# FLASH_S29GL128P11FFI010_128Mbit.net
KiCad netlist of a schematic drawn in Altium Designer
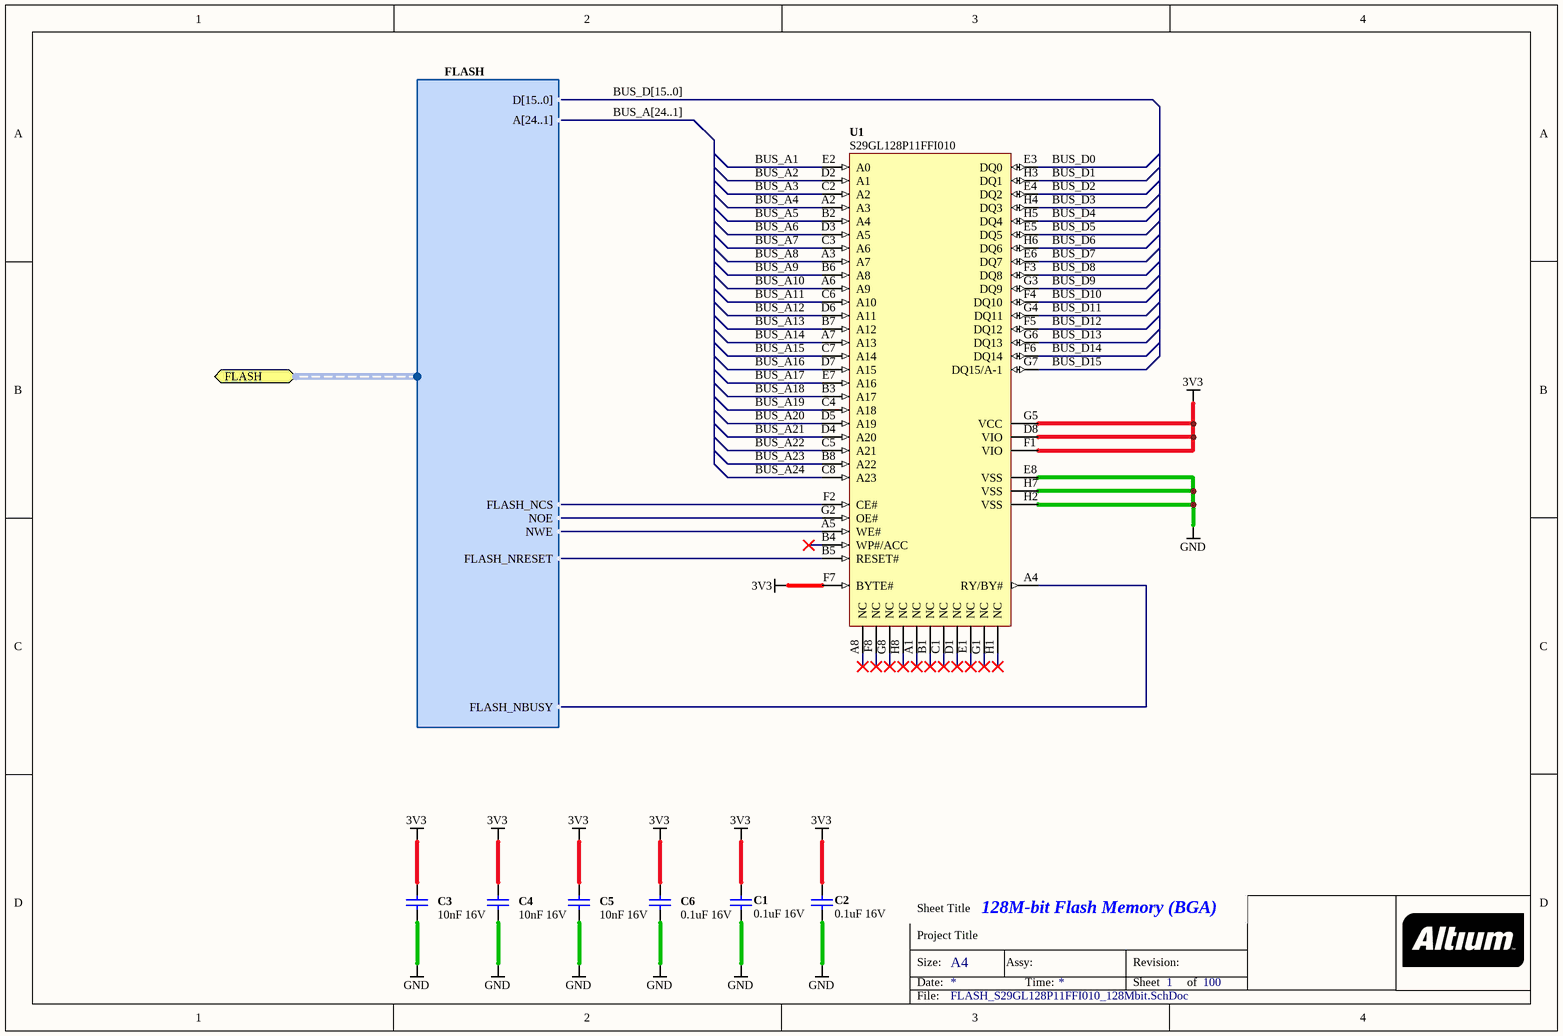
[diagram p0: FLASH_S29GL128P11FFI010_128Mbit.SchDoc]

(export (version "E")
  (design (tool "Eeschema 10.0.6"))
  (components
    (comp (ref "C1")
      (value "0.1uF 16V")
      (footprint "CAPC1005-STAR")
      (description "Capacitor, Ceramic, 0.1uF 10% 16V 0402 (1005) X7R")
      (fields (field (name "TOLERANCE") "10 %"))
      (libsource (lib "altium-import") (part "root_0_mirrored_CAP-NP_"))
    )
    (comp (ref "C2")
      (value "0.1uF 16V")
      (footprint "CAPC1005-STAR")
      (description "Capacitor, Ceramic, 0.1uF 10% 16V 0402 (1005) X7R")
      (fields (field (name "TOLERANCE") "10 %"))
      (libsource (lib "altium-import") (part "root_0_mirrored_CAP-NP_"))
    )
    (comp (ref "C3")
      (value "10nF 16V")
      (footprint "CAPC1005-STAR")
      (description "Capacitor, Ceramic, 10nF 10% 16V 0402 (1005) X7R")
      (fields (field (name "TOLERANCE") "10 %"))
      (libsource (lib "altium-import") (part "root_0_CAP-NP_"))
    )
    (comp (ref "C4")
      (value "10nF 16V")
      (footprint "CAPC1005-STAR")
      (description "Capacitor, Ceramic, 10nF 10% 16V 0402 (1005) X7R")
      (fields (field (name "TOLERANCE") "10 %"))
      (libsource (lib "altium-import") (part "root_0_CAP-NP_"))
    )
    (comp (ref "C5")
      (value "10nF 16V")
      (footprint "CAPC1005-STAR")
      (description "Capacitor, Ceramic, 10nF 10% 16V 0402 (1005) X7R")
      (fields (field (name "TOLERANCE") "10 %"))
      (libsource (lib "altium-import") (part "root_0_CAP-NP_"))
    )
    (comp (ref "C6")
      (value "0.1uF 16V")
      (footprint "CAPC1005-STAR")
      (description "Capacitor, Ceramic, 0.1uF 10% 16V 0402 (1005) X7R")
      (fields (field (name "TOLERANCE") "10 %"))
      (libsource (lib "altium-import") (part "root_0_CAP-NP_"))
    )
    (comp (ref "U1")
      (value "S29GL128P11FFI010")
      (footprint "BGA100P8X8-64")
      (description "IC Flash, S29GL128P11FFI010 128 Megabit 3.0V Page Mode Flash Memory")
      (libsource (lib "AltiumDesignLibrary") (part "S29GL128P"))
    )
  )
  (nets
    (net (code "2") (name "/BUS_A1") (class "Default")
      (node (ref "U1") (pin "E2") (pinfunction "A0_E2") (pintype "input"))
    )
    (net (code "3") (name "/BUS_A2") (class "Default")
      (node (ref "U1") (pin "D2") (pinfunction "A1_D2") (pintype "input"))
    )
    (net (code "4") (name "/BUS_A3") (class "Default")
      (node (ref "U1") (pin "C2") (pinfunction "A2_C2") (pintype "input"))
    )
    (net (code "5") (name "/BUS_A4") (class "Default")
      (node (ref "U1") (pin "A2") (pinfunction "A3_A2") (pintype "input"))
    )
    (net (code "6") (name "/BUS_A5") (class "Default")
      (node (ref "U1") (pin "B2") (pinfunction "A4_B2") (pintype "input"))
    )
    (net (code "7") (name "/BUS_A6") (class "Default")
      (node (ref "U1") (pin "D3") (pinfunction "A5_D3") (pintype "input"))
    )
    (net (code "8") (name "/BUS_A7") (class "Default")
      (node (ref "U1") (pin "C3") (pinfunction "A6_C3") (pintype "input"))
    )
    (net (code "9") (name "/BUS_A8") (class "Default")
      (node (ref "U1") (pin "A3") (pinfunction "A7_A3") (pintype "input"))
    )
    (net (code "10") (name "/BUS_A9") (class "Default")
      (node (ref "U1") (pin "B6") (pinfunction "A8_B6") (pintype "input"))
    )
    (net (code "11") (name "/BUS_A10") (class "Default")
      (node (ref "U1") (pin "A6") (pinfunction "A9_A6") (pintype "input"))
    )
    (net (code "12") (name "/BUS_A11") (class "Default")
      (node (ref "U1") (pin "C6") (pinfunction "A10_C6") (pintype "input"))
    )
    (net (code "13") (name "/BUS_A12") (class "Default")
      (node (ref "U1") (pin "D6") (pinfunction "A11_D6") (pintype "input"))
    )
    (net (code "14") (name "/BUS_A13") (class "Default")
      (node (ref "U1") (pin "B7") (pinfunction "A12_B7") (pintype "input"))
    )
    (net (code "15") (name "/BUS_A14") (class "Default")
      (node (ref "U1") (pin "A7") (pinfunction "A13_A7") (pintype "input"))
    )
    (net (code "16") (name "/BUS_A15") (class "Default")
      (node (ref "U1") (pin "C7") (pinfunction "A14_C7") (pintype "input"))
    )
    (net (code "17") (name "/BUS_A16") (class "Default")
      (node (ref "U1") (pin "D7") (pinfunction "A15_D7") (pintype "input"))
    )
    (net (code "18") (name "/BUS_A17") (class "Default")
      (node (ref "U1") (pin "E7") (pinfunction "A16_E7") (pintype "input"))
    )
    (net (code "19") (name "/BUS_A18") (class "Default")
      (node (ref "U1") (pin "B3") (pinfunction "A17_B3") (pintype "input"))
    )
    (net (code "20") (name "/BUS_A19") (class "Default")
      (node (ref "U1") (pin "C4") (pinfunction "A18_C4") (pintype "input"))
    )
    (net (code "21") (name "/BUS_A20") (class "Default")
      (node (ref "U1") (pin "D5") (pinfunction "A19_D5") (pintype "input"))
    )
    (net (code "22") (name "/BUS_A21") (class "Default")
      (node (ref "U1") (pin "D4") (pinfunction "A20_D4") (pintype "input"))
    )
    (net (code "23") (name "/BUS_A22") (class "Default")
      (node (ref "U1") (pin "C5") (pinfunction "A21_C5") (pintype "input"))
    )
    (net (code "24") (name "/BUS_A23") (class "Default")
      (node (ref "U1") (pin "B8") (pinfunction "A22_B8") (pintype "input"))
    )
    (net (code "25") (name "/BUS_A24") (class "Default")
      (node (ref "U1") (pin "C8") (pinfunction "A23_C8") (pintype "input"))
    )
    (net (code "27") (name "/BUS_D0") (class "Default")
      (node (ref "U1") (pin "E3") (pinfunction "DQ0_E3") (pintype "bidirectional"))
    )
    (net (code "28") (name "/BUS_D1") (class "Default")
      (node (ref "U1") (pin "H3") (pinfunction "DQ1_H3") (pintype "bidirectional"))
    )
    (net (code "29") (name "/BUS_D2") (class "Default")
      (node (ref "U1") (pin "E4") (pinfunction "DQ2_E4") (pintype "bidirectional"))
    )
    (net (code "30") (name "/BUS_D3") (class "Default")
      (node (ref "U1") (pin "H4") (pinfunction "DQ3_H4") (pintype "bidirectional"))
    )
    (net (code "31") (name "/BUS_D4") (class "Default")
      (node (ref "U1") (pin "H5") (pinfunction "DQ4_H5") (pintype "bidirectional"))
    )
    (net (code "32") (name "/BUS_D5") (class "Default")
      (node (ref "U1") (pin "E5") (pinfunction "DQ5_E5") (pintype "bidirectional"))
    )
    (net (code "33") (name "/BUS_D6") (class "Default")
      (node (ref "U1") (pin "H6") (pinfunction "DQ6_H6") (pintype "bidirectional"))
    )
    (net (code "34") (name "/BUS_D7") (class "Default")
      (node (ref "U1") (pin "E6") (pinfunction "DQ7_E6") (pintype "bidirectional"))
    )
    (net (code "35") (name "/BUS_D8") (class "Default")
      (node (ref "U1") (pin "F3") (pinfunction "DQ8_F3") (pintype "bidirectional"))
    )
    (net (code "36") (name "/BUS_D9") (class "Default")
      (node (ref "U1") (pin "G3") (pinfunction "DQ9_G3") (pintype "bidirectional"))
    )
    (net (code "37") (name "/BUS_D10") (class "Default")
      (node (ref "U1") (pin "F4") (pinfunction "DQ10_F4") (pintype "bidirectional"))
    )
    (net (code "38") (name "/BUS_D11") (class "Default")
      (node (ref "U1") (pin "G4") (pinfunction "DQ11_G4") (pintype "bidirectional"))
    )
    (net (code "39") (name "/BUS_D12") (class "Default")
      (node (ref "U1") (pin "F5") (pinfunction "DQ12_F5") (pintype "bidirectional"))
    )
    (net (code "40") (name "/BUS_D13") (class "Default")
      (node (ref "U1") (pin "G6") (pinfunction "DQ13_G6") (pintype "bidirectional"))
    )
    (net (code "41") (name "/BUS_D14") (class "Default")
      (node (ref "U1") (pin "F6") (pinfunction "DQ14_F6") (pintype "bidirectional"))
    )
    (net (code "42") (name "/BUS_D15") (class "Default")
      (node (ref "U1") (pin "G7") (pinfunction "DQ15/A-1_G7") (pintype "bidirectional"))
    )
    (net (code "44") (name "/FLASH_NBUSY") (class "Default")
      (node (ref "U1") (pin "A4") (pinfunction "RY/BY#_A4") (pintype "output"))
    )
    (net (code "45") (name "/FLASH_NCS") (class "Default")
      (node (ref "U1") (pin "F2") (pinfunction "CE#_F2") (pintype "input"))
    )
    (net (code "46") (name "/FLASH_NRESET") (class "Default")
      (node (ref "U1") (pin "B5") (pinfunction "RESET#_B5") (pintype "input"))
    )
    (net (code "47") (name "/NOE") (class "Default")
      (node (ref "U1") (pin "G2") (pinfunction "OE#_G2") (pintype "input"))
    )
    (net (code "48") (name "/NWE") (class "Default")
      (node (ref "U1") (pin "A5") (pinfunction "WE#_A5") (pintype "input"))
    )
    (net (code "50") (name "3V3") (class "Default")
      (node (ref "C1") (pin "1") (pinfunction "1_1") (pintype "passive"))
      (node (ref "C2") (pin "1") (pinfunction "1_1") (pintype "passive"))
      (node (ref "C3") (pin "1") (pinfunction "1_1") (pintype "passive"))
      (node (ref "C4") (pin "1") (pinfunction "1_1") (pintype "passive"))
      (node (ref "C5") (pin "1") (pinfunction "1_1") (pintype "passive"))
      (node (ref "C6") (pin "1") (pinfunction "1_1") (pintype "passive"))
      (node (ref "U1") (pin "D8") (pinfunction "VIO_D8") (pintype "power_in"))
      (node (ref "U1") (pin "F1") (pinfunction "VIO_F1") (pintype "power_in"))
      (node (ref "U1") (pin "F7") (pinfunction "BYTE#_F7") (pintype "input"))
      (node (ref "U1") (pin "G5") (pinfunction "VCC_G5") (pintype "power_in"))
    )
    (net (code "51") (name "GND") (class "Default")
      (node (ref "C1") (pin "2") (pinfunction "2_2") (pintype "passive"))
      (node (ref "C2") (pin "2") (pinfunction "2_2") (pintype "passive"))
      (node (ref "C3") (pin "2") (pinfunction "2_2") (pintype "passive"))
      (node (ref "C4") (pin "2") (pinfunction "2_2") (pintype "passive"))
      (node (ref "C5") (pin "2") (pinfunction "2_2") (pintype "passive"))
      (node (ref "C6") (pin "2") (pinfunction "2_2") (pintype "passive"))
      (node (ref "U1") (pin "E8") (pinfunction "VSS_E8") (pintype "power_in"))
      (node (ref "U1") (pin "H2") (pinfunction "VSS_H2") (pintype "power_in"))
      (node (ref "U1") (pin "H7") (pinfunction "VSS_H7") (pintype "power_in"))
    )
    (net (code "52") (name "unconnected-(U1-NC-PadA1)") (class "Default")
      (node (ref "U1") (pin "A1") (pinfunction "NC_A1") (pintype "passive+no_connect"))
    )
    (net (code "53") (name "unconnected-(U1-NC-PadA8)") (class "Default")
      (node (ref "U1") (pin "A8") (pinfunction "NC_A8") (pintype "passive+no_connect"))
    )
    (net (code "54") (name "unconnected-(U1-NC-PadB1)") (class "Default")
      (node (ref "U1") (pin "B1") (pinfunction "NC_B1") (pintype "passive+no_connect"))
    )
    (net (code "55") (name "unconnected-(U1-NC-PadC1)") (class "Default")
      (node (ref "U1") (pin "C1") (pinfunction "NC_C1") (pintype "passive+no_connect"))
    )
    (net (code "56") (name "unconnected-(U1-NC-PadD1)") (class "Default")
      (node (ref "U1") (pin "D1") (pinfunction "NC_D1") (pintype "passive+no_connect"))
    )
    (net (code "57") (name "unconnected-(U1-NC-PadE1)") (class "Default")
      (node (ref "U1") (pin "E1") (pinfunction "NC_E1") (pintype "passive+no_connect"))
    )
    (net (code "58") (name "unconnected-(U1-NC-PadF8)") (class "Default")
      (node (ref "U1") (pin "F8") (pinfunction "NC_F8") (pintype "passive+no_connect"))
    )
    (net (code "59") (name "unconnected-(U1-NC-PadG1)") (class "Default")
      (node (ref "U1") (pin "G1") (pinfunction "NC_G1") (pintype "passive+no_connect"))
    )
    (net (code "60") (name "unconnected-(U1-NC-PadG8)") (class "Default")
      (node (ref "U1") (pin "G8") (pinfunction "NC_G8") (pintype "passive+no_connect"))
    )
    (net (code "61") (name "unconnected-(U1-NC-PadH1)") (class "Default")
      (node (ref "U1") (pin "H1") (pinfunction "NC_H1") (pintype "passive+no_connect"))
    )
    (net (code "62") (name "unconnected-(U1-NC-PadH8)") (class "Default")
      (node (ref "U1") (pin "H8") (pinfunction "NC_H8") (pintype "passive+no_connect"))
    )
    (net (code "63") (name "unconnected-(U1-WP#{slash}ACC-PadB4)") (class "Default")
      (node (ref "U1") (pin "B4") (pinfunction "WP#/ACC_B4") (pintype "input+no_connect"))
    )
  )
)
